# DAC.net
KiCad netlist of a schematic drawn in Altium Designer
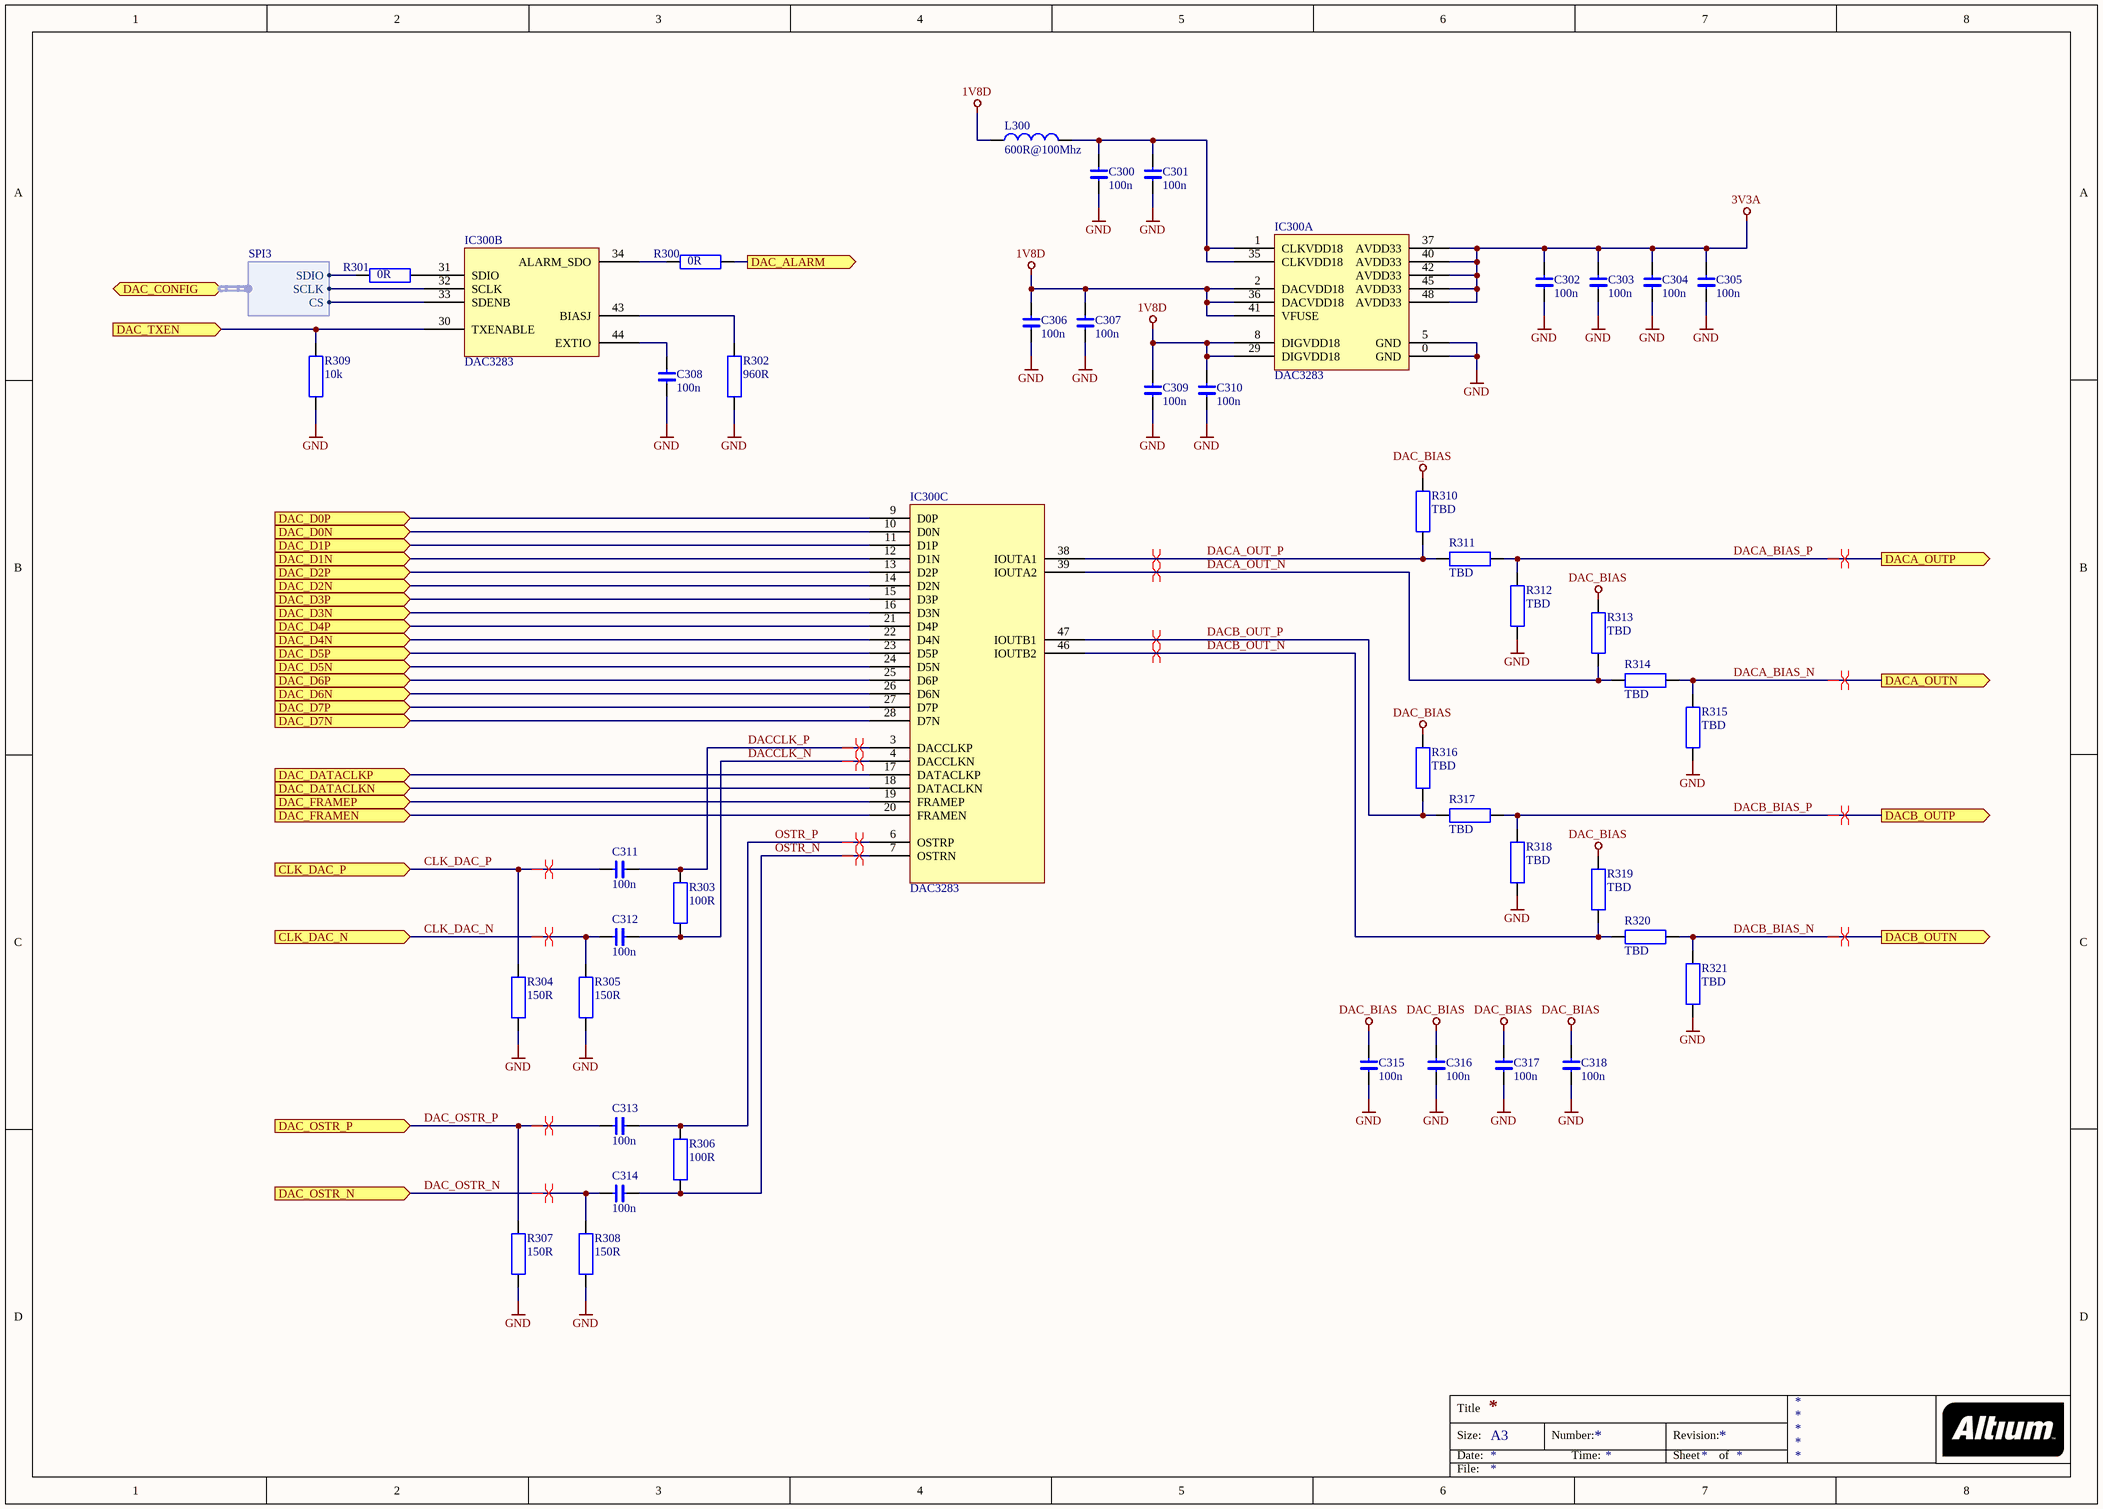
[diagram p0: DAC.SchDoc]

(export (version "E")
  (design (tool "Eeschema 10.0.6"))
  (components
    (comp (ref "C300")
      (value "100n")
      (footprint "0603 SMALL OUTLINE")
      (description "C")
      (libsource (lib "RCL") (part "C"))
    )
    (comp (ref "C301")
      (value "100n")
      (footprint "0603 SMALL OUTLINE")
      (description "C")
      (libsource (lib "RCL") (part "C"))
    )
    (comp (ref "C302")
      (value "100n")
      (footprint "0603 SMALL OUTLINE")
      (description "C")
      (libsource (lib "RCL") (part "C"))
    )
    (comp (ref "C303")
      (value "100n")
      (footprint "0603 SMALL OUTLINE")
      (description "C")
      (libsource (lib "RCL") (part "C"))
    )
    (comp (ref "C304")
      (value "100n")
      (footprint "0603 SMALL OUTLINE")
      (description "C")
      (libsource (lib "RCL") (part "C"))
    )
    (comp (ref "C305")
      (value "100n")
      (footprint "0603 SMALL OUTLINE")
      (description "C")
      (libsource (lib "RCL") (part "C"))
    )
    (comp (ref "C306")
      (value "100n")
      (footprint "0603 SMALL OUTLINE")
      (description "C")
      (libsource (lib "RCL") (part "C"))
    )
    (comp (ref "C307")
      (value "100n")
      (footprint "0603 SMALL OUTLINE")
      (description "C")
      (libsource (lib "RCL") (part "C"))
    )
    (comp (ref "C308")
      (value "100n")
      (footprint "0603 SMALL OUTLINE")
      (description "C")
      (libsource (lib "RCL") (part "C"))
    )
    (comp (ref "C309")
      (value "100n")
      (footprint "0603 SMALL OUTLINE")
      (description "C")
      (libsource (lib "RCL") (part "C"))
    )
    (comp (ref "C310")
      (value "100n")
      (footprint "0603 SMALL OUTLINE")
      (description "C")
      (libsource (lib "RCL") (part "C"))
    )
    (comp (ref "C311")
      (value "100n")
      (footprint "0603 SMALL OUTLINE")
      (description "C")
      (libsource (lib "RCL") (part "C"))
    )
    (comp (ref "C312")
      (value "100n")
      (footprint "0603 SMALL OUTLINE")
      (description "C")
      (libsource (lib "RCL") (part "C"))
    )
    (comp (ref "C313")
      (value "100n")
      (footprint "0603 SMALL OUTLINE")
      (description "C")
      (libsource (lib "RCL") (part "C"))
    )
    (comp (ref "C314")
      (value "100n")
      (footprint "0603 SMALL OUTLINE")
      (description "C")
      (libsource (lib "RCL") (part "C"))
    )
    (comp (ref "C315")
      (value "100n")
      (footprint "0603 SMALL OUTLINE")
      (description "C")
      (libsource (lib "RCL") (part "C"))
    )
    (comp (ref "C316")
      (value "100n")
      (footprint "0603 SMALL OUTLINE")
      (description "C")
      (libsource (lib "RCL") (part "C"))
    )
    (comp (ref "C317")
      (value "100n")
      (footprint "0603 SMALL OUTLINE")
      (description "C")
      (libsource (lib "RCL") (part "C"))
    )
    (comp (ref "C318")
      (value "100n")
      (footprint "0603 SMALL OUTLINE")
      (description "C")
      (libsource (lib "RCL") (part "C"))
    )
    (comp (ref "IC300")
      (value "DAC3283")
      (footprint "VQFN48_LONG")
      (description "Dual-Channel,  16-Bit,  800  MSPS,  Digital-to-Analog  Converter  (DAC)")
      (libsource (lib "Private") (part "DAC3283"))
    )
    (comp (ref "L300") (value "600R@100Mhz") (footprint "0805") (libsource (lib "RCL") (part "L")))
    (comp (ref "R300")
      (value "0R")
      (footprint "0603 SMALL OUTLINE")
      (description "R")
      (libsource (lib "RCL") (part "R"))
    )
    (comp (ref "R301")
      (value "0R")
      (footprint "0603 SMALL OUTLINE")
      (description "R")
      (libsource (lib "RCL") (part "R"))
    )
    (comp (ref "R302")
      (value "960R")
      (footprint "0603 SMALL OUTLINE")
      (description "R")
      (libsource (lib "RCL") (part "R"))
    )
    (comp (ref "R303")
      (value "100R")
      (footprint "0603 SMALL OUTLINE")
      (description "R")
      (libsource (lib "RCL") (part "R"))
    )
    (comp (ref "R304")
      (value "150R")
      (footprint "0603 SMALL OUTLINE")
      (description "R")
      (libsource (lib "RCL") (part "R"))
    )
    (comp (ref "R305")
      (value "150R")
      (footprint "0603 SMALL OUTLINE")
      (description "R")
      (libsource (lib "RCL") (part "R"))
    )
    (comp (ref "R306")
      (value "100R")
      (footprint "0603 SMALL OUTLINE")
      (description "R")
      (libsource (lib "RCL") (part "R"))
    )
    (comp (ref "R307")
      (value "150R")
      (footprint "0603 SMALL OUTLINE")
      (description "R")
      (libsource (lib "RCL") (part "R"))
    )
    (comp (ref "R308")
      (value "150R")
      (footprint "0603 SMALL OUTLINE")
      (description "R")
      (libsource (lib "RCL") (part "R"))
    )
    (comp (ref "R309")
      (value "10k")
      (footprint "0603 SMALL OUTLINE")
      (description "R")
      (libsource (lib "RCL") (part "R"))
    )
    (comp (ref "R310")
      (value "TBD")
      (footprint "0603 SMALL OUTLINE")
      (description "R")
      (libsource (lib "RCL") (part "R"))
    )
    (comp (ref "R311")
      (value "TBD")
      (footprint "0603 SMALL OUTLINE")
      (description "R")
      (libsource (lib "RCL") (part "R"))
    )
    (comp (ref "R312")
      (value "TBD")
      (footprint "0603 SMALL OUTLINE")
      (description "R")
      (libsource (lib "RCL") (part "R"))
    )
    (comp (ref "R313")
      (value "TBD")
      (footprint "0603 SMALL OUTLINE")
      (description "R")
      (libsource (lib "RCL") (part "R"))
    )
    (comp (ref "R314")
      (value "TBD")
      (footprint "0603 SMALL OUTLINE")
      (description "R")
      (libsource (lib "RCL") (part "R"))
    )
    (comp (ref "R315")
      (value "TBD")
      (footprint "0603 SMALL OUTLINE")
      (description "R")
      (libsource (lib "RCL") (part "R"))
    )
    (comp (ref "R316")
      (value "TBD")
      (footprint "0603 SMALL OUTLINE")
      (description "R")
      (libsource (lib "RCL") (part "R"))
    )
    (comp (ref "R317")
      (value "TBD")
      (footprint "0603 SMALL OUTLINE")
      (description "R")
      (libsource (lib "RCL") (part "R"))
    )
    (comp (ref "R318")
      (value "TBD")
      (footprint "0603 SMALL OUTLINE")
      (description "R")
      (libsource (lib "RCL") (part "R"))
    )
    (comp (ref "R319")
      (value "TBD")
      (footprint "0603 SMALL OUTLINE")
      (description "R")
      (libsource (lib "RCL") (part "R"))
    )
    (comp (ref "R320")
      (value "TBD")
      (footprint "0603 SMALL OUTLINE")
      (description "R")
      (libsource (lib "RCL") (part "R"))
    )
    (comp (ref "R321")
      (value "TBD")
      (footprint "0603 SMALL OUTLINE")
      (description "R")
      (libsource (lib "RCL") (part "R"))
    )
  )
  (nets
    (net (code "2") (name "/CLK_DAC_N") (class "Default")
      (node (ref "C312") (pin "1") (pinfunction "1_1") (pintype "passive"))
      (node (ref "R305") (pin "1") (pinfunction "1_1") (pintype "passive"))
    )
    (net (code "3") (name "/CLK_DAC_P") (class "Default")
      (node (ref "C311") (pin "1") (pinfunction "1_1") (pintype "passive"))
      (node (ref "R304") (pin "1") (pinfunction "1_1") (pintype "passive"))
    )
    (net (code "4") (name "/CS") (class "Default")
      (node (ref "IC300") (pin "33") (pinfunction "SDENB_33") (pintype "passive"))
    )
    (net (code "5") (name "/DACA_BIAS_N") (class "Default")
      (node (ref "R314") (pin "2") (pinfunction "2_2") (pintype "passive"))
      (node (ref "R315") (pin "1") (pinfunction "1_1") (pintype "passive"))
    )
    (net (code "6") (name "/DACA_BIAS_P") (class "Default")
      (node (ref "R311") (pin "2") (pinfunction "2_2") (pintype "passive"))
      (node (ref "R312") (pin "1") (pinfunction "1_1") (pintype "passive"))
    )
    (net (code "7") (name "/DACA_OUT_N") (class "Default")
      (node (ref "IC300") (pin "39") (pinfunction "IOUTA2_39") (pintype "passive"))
      (node (ref "R313") (pin "2") (pinfunction "2_2") (pintype "passive"))
      (node (ref "R314") (pin "1") (pinfunction "1_1") (pintype "passive"))
    )
    (net (code "8") (name "/DACA_OUT_P") (class "Default")
      (node (ref "IC300") (pin "38") (pinfunction "IOUTA1_38") (pintype "passive"))
      (node (ref "R310") (pin "2") (pinfunction "2_2") (pintype "passive"))
      (node (ref "R311") (pin "1") (pinfunction "1_1") (pintype "passive"))
    )
    (net (code "9") (name "/DACB_BIAS_N") (class "Default")
      (node (ref "R320") (pin "2") (pinfunction "2_2") (pintype "passive"))
      (node (ref "R321") (pin "1") (pinfunction "1_1") (pintype "passive"))
    )
    (net (code "10") (name "/DACB_BIAS_P") (class "Default")
      (node (ref "R317") (pin "2") (pinfunction "2_2") (pintype "passive"))
      (node (ref "R318") (pin "1") (pinfunction "1_1") (pintype "passive"))
    )
    (net (code "11") (name "/DACB_OUT_N") (class "Default")
      (node (ref "IC300") (pin "46") (pinfunction "IOUTB2_46") (pintype "passive"))
      (node (ref "R319") (pin "2") (pinfunction "2_2") (pintype "passive"))
      (node (ref "R320") (pin "1") (pinfunction "1_1") (pintype "passive"))
    )
    (net (code "12") (name "/DACB_OUT_P") (class "Default")
      (node (ref "IC300") (pin "47") (pinfunction "IOUTB1_47") (pintype "passive"))
      (node (ref "R316") (pin "2") (pinfunction "2_2") (pintype "passive"))
      (node (ref "R317") (pin "1") (pinfunction "1_1") (pintype "passive"))
    )
    (net (code "13") (name "/DACCLK_N") (class "Default")
      (node (ref "C312") (pin "2") (pinfunction "2_2") (pintype "passive"))
      (node (ref "IC300") (pin "4") (pinfunction "DACCLKN_4") (pintype "passive"))
      (node (ref "R303") (pin "2") (pinfunction "2_2") (pintype "passive"))
    )
    (net (code "14") (name "/DACCLK_P") (class "Default")
      (node (ref "C311") (pin "2") (pinfunction "2_2") (pintype "passive"))
      (node (ref "IC300") (pin "3") (pinfunction "DACCLKP_3") (pintype "passive"))
      (node (ref "R303") (pin "1") (pinfunction "1_1") (pintype "passive"))
    )
    (net (code "15") (name "/DAC_ALARM") (class "Default")
      (node (ref "R300") (pin "2") (pinfunction "2_2") (pintype "passive"))
    )
    (net (code "16") (name "/DAC_D0N") (class "Default")
      (node (ref "IC300") (pin "10") (pinfunction "D0N_10") (pintype "passive"))
    )
    (net (code "17") (name "/DAC_D0P") (class "Default")
      (node (ref "IC300") (pin "9") (pinfunction "D0P_9") (pintype "passive"))
    )
    (net (code "18") (name "/DAC_D1N") (class "Default")
      (node (ref "IC300") (pin "12") (pinfunction "D1N_12") (pintype "passive"))
    )
    (net (code "19") (name "/DAC_D1P") (class "Default")
      (node (ref "IC300") (pin "11") (pinfunction "D1P_11") (pintype "passive"))
    )
    (net (code "20") (name "/DAC_D2N") (class "Default")
      (node (ref "IC300") (pin "14") (pinfunction "D2N_14") (pintype "passive"))
    )
    (net (code "21") (name "/DAC_D2P") (class "Default")
      (node (ref "IC300") (pin "13") (pinfunction "D2P_13") (pintype "passive"))
    )
    (net (code "22") (name "/DAC_D3N") (class "Default")
      (node (ref "IC300") (pin "16") (pinfunction "D3N_16") (pintype "passive"))
    )
    (net (code "23") (name "/DAC_D3P") (class "Default")
      (node (ref "IC300") (pin "15") (pinfunction "D3P_15") (pintype "passive"))
    )
    (net (code "24") (name "/DAC_D4N") (class "Default")
      (node (ref "IC300") (pin "22") (pinfunction "D4N_22") (pintype "passive"))
    )
    (net (code "25") (name "/DAC_D4P") (class "Default")
      (node (ref "IC300") (pin "21") (pinfunction "D4P_21") (pintype "passive"))
    )
    (net (code "26") (name "/DAC_D5N") (class "Default")
      (node (ref "IC300") (pin "24") (pinfunction "D5N_24") (pintype "passive"))
    )
    (net (code "27") (name "/DAC_D5P") (class "Default")
      (node (ref "IC300") (pin "23") (pinfunction "D5P_23") (pintype "passive"))
    )
    (net (code "28") (name "/DAC_D6N") (class "Default")
      (node (ref "IC300") (pin "26") (pinfunction "D6N_26") (pintype "passive"))
    )
    (net (code "29") (name "/DAC_D6P") (class "Default")
      (node (ref "IC300") (pin "25") (pinfunction "D6P_25") (pintype "passive"))
    )
    (net (code "30") (name "/DAC_D7N") (class "Default")
      (node (ref "IC300") (pin "28") (pinfunction "D7N_28") (pintype "passive"))
    )
    (net (code "31") (name "/DAC_D7P") (class "Default")
      (node (ref "IC300") (pin "27") (pinfunction "D7P_27") (pintype "passive"))
    )
    (net (code "32") (name "/DAC_DATACLKN") (class "Default")
      (node (ref "IC300") (pin "18") (pinfunction "DATACLKN_18") (pintype "passive"))
    )
    (net (code "33") (name "/DAC_DATACLKP") (class "Default")
      (node (ref "IC300") (pin "17") (pinfunction "DATACLKP_17") (pintype "passive"))
    )
    (net (code "34") (name "/DAC_FRAMEN") (class "Default")
      (node (ref "IC300") (pin "20") (pinfunction "FRAMEN_20") (pintype "passive"))
    )
    (net (code "35") (name "/DAC_FRAMEP") (class "Default")
      (node (ref "IC300") (pin "19") (pinfunction "FRAMEP_19") (pintype "passive"))
    )
    (net (code "36") (name "/DAC_OSTR_N") (class "Default")
      (node (ref "C314") (pin "1") (pinfunction "1_1") (pintype "passive"))
      (node (ref "R308") (pin "1") (pinfunction "1_1") (pintype "passive"))
    )
    (net (code "37") (name "/DAC_OSTR_P") (class "Default")
      (node (ref "C313") (pin "1") (pinfunction "1_1") (pintype "passive"))
      (node (ref "R307") (pin "1") (pinfunction "1_1") (pintype "passive"))
    )
    (net (code "38") (name "/DAC_TXEN") (class "Default")
      (node (ref "IC300") (pin "30") (pinfunction "TXENABLE_30") (pintype "passive"))
      (node (ref "R309") (pin "1") (pinfunction "1_1") (pintype "passive"))
    )
    (net (code "39") (name "/OSTR_N") (class "Default")
      (node (ref "C314") (pin "2") (pinfunction "2_2") (pintype "passive"))
      (node (ref "IC300") (pin "7") (pinfunction "OSTRN_7") (pintype "passive"))
      (node (ref "R306") (pin "2") (pinfunction "2_2") (pintype "passive"))
    )
    (net (code "40") (name "/OSTR_P") (class "Default")
      (node (ref "C313") (pin "2") (pinfunction "2_2") (pintype "passive"))
      (node (ref "IC300") (pin "6") (pinfunction "OSTRP_6") (pintype "passive"))
      (node (ref "R306") (pin "1") (pinfunction "1_1") (pintype "passive"))
    )
    (net (code "41") (name "/SCLK") (class "Default")
      (node (ref "IC300") (pin "32") (pinfunction "SCLK_32") (pintype "passive"))
    )
    (net (code "42") (name "/SDIO") (class "Default")
      (node (ref "R301") (pin "1") (pinfunction "1_1") (pintype "passive"))
    )
    (net (code "44") (name "1V8D") (class "Default")
      (node (ref "C306") (pin "1") (pinfunction "1_1") (pintype "passive"))
      (node (ref "C307") (pin "1") (pinfunction "1_1") (pintype "passive"))
      (node (ref "C309") (pin "1") (pinfunction "1_1") (pintype "passive"))
      (node (ref "C310") (pin "1") (pinfunction "1_1") (pintype "passive"))
      (node (ref "IC300") (pin "2") (pinfunction "DACVDD18_2") (pintype "passive"))
      (node (ref "IC300") (pin "29") (pinfunction "DIGVDD18_29") (pintype "passive"))
      (node (ref "IC300") (pin "36") (pinfunction "DACVDD18_36") (pintype "passive"))
      (node (ref "IC300") (pin "41") (pinfunction "VFUSE_41") (pintype "passive"))
      (node (ref "IC300") (pin "8") (pinfunction "DIGVDD18_8") (pintype "passive"))
      (node (ref "L300") (pin "1") (pinfunction "1_1") (pintype "passive"))
    )
    (net (code "45") (name "3V3A") (class "Default")
      (node (ref "C302") (pin "1") (pinfunction "1_1") (pintype "passive"))
      (node (ref "C303") (pin "1") (pinfunction "1_1") (pintype "passive"))
      (node (ref "C304") (pin "1") (pinfunction "1_1") (pintype "passive"))
      (node (ref "C305") (pin "1") (pinfunction "1_1") (pintype "passive"))
      (node (ref "IC300") (pin "37") (pinfunction "AVDD33_37") (pintype "passive"))
      (node (ref "IC300") (pin "40") (pinfunction "AVDD33_40") (pintype "passive"))
      (node (ref "IC300") (pin "42") (pinfunction "AVDD33_42") (pintype "passive"))
      (node (ref "IC300") (pin "45") (pinfunction "AVDD33_45") (pintype "passive"))
      (node (ref "IC300") (pin "48") (pinfunction "AVDD33_48") (pintype "passive"))
    )
    (net (code "46") (name "DAC_BIAS") (class "Default")
      (node (ref "C315") (pin "1") (pinfunction "1_1") (pintype "passive"))
      (node (ref "C316") (pin "1") (pinfunction "1_1") (pintype "passive"))
      (node (ref "C317") (pin "1") (pinfunction "1_1") (pintype "passive"))
      (node (ref "C318") (pin "1") (pinfunction "1_1") (pintype "passive"))
      (node (ref "R310") (pin "1") (pinfunction "1_1") (pintype "passive"))
      (node (ref "R313") (pin "1") (pinfunction "1_1") (pintype "passive"))
      (node (ref "R316") (pin "1") (pinfunction "1_1") (pintype "passive"))
      (node (ref "R319") (pin "1") (pinfunction "1_1") (pintype "passive"))
    )
    (net (code "47") (name "GND") (class "Default")
      (node (ref "C300") (pin "2") (pinfunction "2_2") (pintype "passive"))
      (node (ref "C301") (pin "2") (pinfunction "2_2") (pintype "passive"))
      (node (ref "C302") (pin "2") (pinfunction "2_2") (pintype "passive"))
      (node (ref "C303") (pin "2") (pinfunction "2_2") (pintype "passive"))
      (node (ref "C304") (pin "2") (pinfunction "2_2") (pintype "passive"))
      (node (ref "C305") (pin "2") (pinfunction "2_2") (pintype "passive"))
      (node (ref "C306") (pin "2") (pinfunction "2_2") (pintype "passive"))
      (node (ref "C307") (pin "2") (pinfunction "2_2") (pintype "passive"))
      (node (ref "C308") (pin "1") (pinfunction "1_1") (pintype "passive"))
      (node (ref "C309") (pin "2") (pinfunction "2_2") (pintype "passive"))
      (node (ref "C310") (pin "2") (pinfunction "2_2") (pintype "passive"))
      (node (ref "C315") (pin "2") (pinfunction "2_2") (pintype "passive"))
      (node (ref "C316") (pin "2") (pinfunction "2_2") (pintype "passive"))
      (node (ref "C317") (pin "2") (pinfunction "2_2") (pintype "passive"))
      (node (ref "C318") (pin "2") (pinfunction "2_2") (pintype "passive"))
      (node (ref "IC300") (pin "0") (pinfunction "GND_0") (pintype "passive"))
      (node (ref "IC300") (pin "5") (pinfunction "GND_5") (pintype "passive"))
      (node (ref "R302") (pin "2") (pinfunction "2_2") (pintype "passive"))
      (node (ref "R304") (pin "2") (pinfunction "2_2") (pintype "passive"))
      (node (ref "R305") (pin "2") (pinfunction "2_2") (pintype "passive"))
      (node (ref "R307") (pin "2") (pinfunction "2_2") (pintype "passive"))
      (node (ref "R308") (pin "2") (pinfunction "2_2") (pintype "passive"))
      (node (ref "R309") (pin "2") (pinfunction "2_2") (pintype "passive"))
      (node (ref "R312") (pin "2") (pinfunction "2_2") (pintype "passive"))
      (node (ref "R315") (pin "2") (pinfunction "2_2") (pintype "passive"))
      (node (ref "R318") (pin "2") (pinfunction "2_2") (pintype "passive"))
      (node (ref "R321") (pin "2") (pinfunction "2_2") (pintype "passive"))
    )
    (net (code "48") (name "Net-(C300-Pad1)") (class "Default")
      (node (ref "C300") (pin "1") (pinfunction "1_1") (pintype "passive"))
      (node (ref "C301") (pin "1") (pinfunction "1_1") (pintype "passive"))
      (node (ref "IC300") (pin "1") (pinfunction "CLKVDD18_1") (pintype "passive"))
      (node (ref "IC300") (pin "35") (pinfunction "CLKVDD18_35") (pintype "passive"))
      (node (ref "L300") (pin "2") (pinfunction "2_2") (pintype "passive"))
    )
    (net (code "49") (name "Net-(IC300B-ALARM_SDO)") (class "Default")
      (node (ref "IC300") (pin "34") (pinfunction "ALARM_SDO_34") (pintype "passive"))
      (node (ref "R300") (pin "1") (pinfunction "1_1") (pintype "passive"))
    )
    (net (code "50") (name "Net-(IC300B-BIASJ)") (class "Default")
      (node (ref "IC300") (pin "43") (pinfunction "BIASJ_43") (pintype "passive"))
      (node (ref "R302") (pin "1") (pinfunction "1_1") (pintype "passive"))
    )
    (net (code "51") (name "Net-(IC300B-EXTIO)") (class "Default")
      (node (ref "C308") (pin "2") (pinfunction "2_2") (pintype "passive"))
      (node (ref "IC300") (pin "44") (pinfunction "EXTIO_44") (pintype "passive"))
    )
    (net (code "52") (name "Net-(IC300B-SDIO)") (class "Default")
      (node (ref "IC300") (pin "31") (pinfunction "SDIO_31") (pintype "passive"))
      (node (ref "R301") (pin "2") (pinfunction "2_2") (pintype "passive"))
    )
  )
)
